# 03_pushswitch.net
KiCad netlist of a schematic drawn in Altium Designer
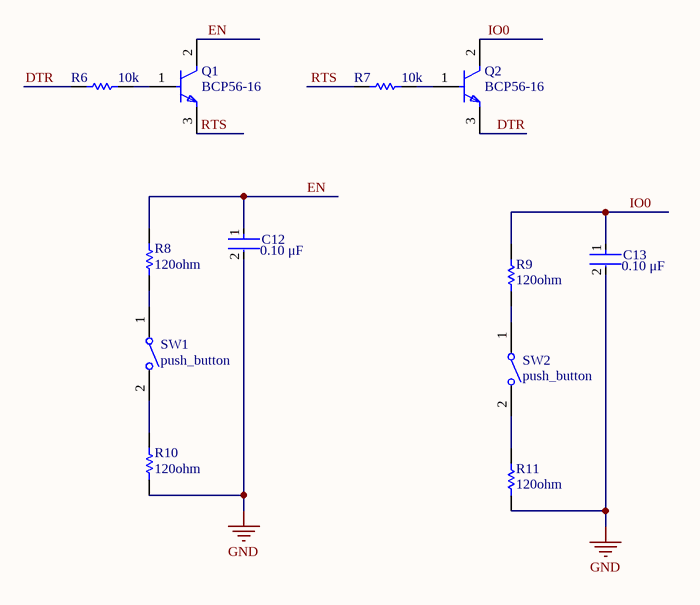
[diagram p0: 03_pushswitch.SchDoc]

(export (version "E")
  (design (tool "Eeschema 10.0.6"))
  (components
    (comp (ref "C12")
      (value "C0603_0.1UF")
      (footprint "FP-C0603C-CF-MFG")
      (description "CAP CER 0.1UF 16V X7R 0603")
      (fields
        (field (name "TOLERANCE") "0.2")
        (field (name "CAPACITANCE") "0.10 μF")
        (field (name "MANUFACTURER PART NUMBER") "C0603C104M4RAC7411")
      )
      (libsource (lib "Altium Content Vault") (part "b4654b650e69147ec39a6b967a45e02"))
    )
    (comp (ref "C13")
      (value "C0603_0.1UF")
      (footprint "FP-C0603C-CF-MFG")
      (description "CAP CER 0.1UF 16V X7R 0603")
      (fields
        (field (name "TOLERANCE") "0.2")
        (field (name "CAPACITANCE") "0.10 μF")
        (field (name "MANUFACTURER PART NUMBER") "C0603C104M4RAC7411")
      )
      (libsource (lib "Altium Content Vault") (part "b4654b650e69147ec39a6b967a45e02"))
    )
    (comp (ref "Q1")
      (value "BCP56-16")
      (footprint "FP-SOT-223-P008-MFG")
      (description "TRANS NPN 80V 1A SOT-223")
      (fields
        (field (name "OCTOPART") "https://octopart.com/bcp56-16-stmicroelectronics-13883839")
        (field (name "MANUFACTURER") "STMicroelectronics")
      )
      (libsource (lib "Altium Content Vault") (part "1c57d9dae74fe2702546667b0e849db"))
    )
    (comp (ref "Q2")
      (value "BCP56-16")
      (footprint "FP-SOT-223-P008-MFG")
      (description "TRANS NPN 80V 1A SOT-223")
      (fields
        (field (name "OCTOPART") "https://octopart.com/bcp56-16-stmicroelectronics-13883839")
        (field (name "MANUFACTURER") "STMicroelectronics")
      )
      (libsource (lib "Altium Content Vault") (part "1c57d9dae74fe2702546667b0e849db"))
    )
    (comp (ref "R6")
      (value "10k")
      (footprint "RESC1609X55X30LL15T15")
      (description "Chip Resistor, 10 KOhm, +/- 1%, 0.1 W, -55 to 155 degC, 0603 (1608 Metric), RoHS, Tape and Reel")
      (fields (field (name "TOLERANCE") "1%") (field (name "MANUFACTURER") "Panasonic"))
      (libsource (lib "Altium Content Vault") (part "RES-2"))
    )
    (comp (ref "R7")
      (value "10k")
      (footprint "RESC1609X55X30LL15T15")
      (description "Chip Resistor, 10 KOhm, +/- 1%, 0.1 W, -55 to 155 degC, 0603 (1608 Metric), RoHS, Tape and Reel")
      (fields (field (name "TOLERANCE") "1%") (field (name "MANUFACTURER") "Panasonic"))
      (libsource (lib "Altium Content Vault") (part "RES-2"))
    )
    (comp (ref "R8")
      (value "120ohm")
      (footprint "RESC1608X55X30NL20T20")
      (fields
        (field (name "PART NUMBER") "ERA-3AEB121V")
        (field (name "MANUFACTURER") "Panasonic")
        (field (name "Comment") "R0603_120R")
      )
      (libsource (lib "Altium Content Vault") (part "RES"))
    )
    (comp (ref "R9")
      (value "120ohm")
      (footprint "RESC1608X55X30NL20T20")
      (fields
        (field (name "PART NUMBER") "ERA-3AEB121V")
        (field (name "MANUFACTURER") "Panasonic")
        (field (name "Comment") "R0603_120R")
      )
      (libsource (lib "Altium Content Vault") (part "RES"))
    )
    (comp (ref "R10")
      (value "120ohm")
      (footprint "RESC1608X55X30NL20T20")
      (fields
        (field (name "PART NUMBER") "ERA-3AEB121V")
        (field (name "MANUFACTURER") "Panasonic")
        (field (name "Comment") "R0603_120R")
      )
      (libsource (lib "Altium Content Vault") (part "RES"))
    )
    (comp (ref "R11")
      (value "120ohm")
      (footprint "RESC1608X55X30NL20T20")
      (fields
        (field (name "PART NUMBER") "ERA-3AEB121V")
        (field (name "MANUFACTURER") "Panasonic")
        (field (name "Comment") "R0603_120R")
      )
      (libsource (lib "Altium Content Vault") (part "RES"))
    )
    (comp (ref "SW1")
      (value "push_button")
      (footprint "TECO-FSMSMTR_V")
      (description "FSMSM Push Button Switch, 50 mA, -35 to 85 degC, 2-Pin SMD, RoHS, Tape and Reel")
      (fields (field (name "MANUFACTURER") "TE Connectivity"))
      (libsource (lib "Altium Content Vault") (part "SW-SPST-2_C"))
    )
    (comp (ref "SW2")
      (value "push_button")
      (footprint "TECO-FSMSMTR_V")
      (description "FSMSM Push Button Switch, 50 mA, -35 to 85 degC, 2-Pin SMD, RoHS, Tape and Reel")
      (fields (field (name "MANUFACTURER") "TE Connectivity"))
      (libsource (lib "Altium Content Vault") (part "SW-SPST-2_C"))
    )
  )
  (nets
    (net (code "1") (name "/DTR") (class "Default")
      (node (ref "Q2") (pin "3") (pinfunction "E_3") (pintype "passive"))
      (node (ref "R6") (pin "1") (pinfunction "1_1") (pintype "passive"))
    )
    (net (code "2") (name "/EN") (class "Default")
      (node (ref "C12") (pin "1") (pinfunction "1_1") (pintype "passive"))
      (node (ref "Q1") (pin "2") (pinfunction "C_2") (pintype "passive"))
      (node (ref "R8") (pin "2") (pinfunction "2_2") (pintype "passive"))
    )
    (net (code "3") (name "/IO0") (class "Default")
      (node (ref "C13") (pin "1") (pinfunction "1_1") (pintype "passive"))
      (node (ref "Q2") (pin "2") (pinfunction "C_2") (pintype "passive"))
      (node (ref "R9") (pin "2") (pinfunction "2_2") (pintype "passive"))
    )
    (net (code "4") (name "/RTS") (class "Default")
      (node (ref "Q1") (pin "3") (pinfunction "E_3") (pintype "passive"))
      (node (ref "R7") (pin "1") (pinfunction "1_1") (pintype "passive"))
    )
    (net (code "5") (name "GND") (class "Default")
      (node (ref "C12") (pin "2") (pinfunction "2_2") (pintype "passive"))
      (node (ref "C13") (pin "2") (pinfunction "2_2") (pintype "passive"))
      (node (ref "R10") (pin "1") (pinfunction "1_1") (pintype "passive"))
      (node (ref "R11") (pin "1") (pinfunction "1_1") (pintype "passive"))
    )
    (net (code "6") (name "Net-(Q1-B)") (class "Default")
      (node (ref "Q1") (pin "1") (pinfunction "B_1") (pintype "passive"))
      (node (ref "R6") (pin "2") (pinfunction "2_2") (pintype "passive"))
    )
    (net (code "7") (name "Net-(Q2-B)") (class "Default")
      (node (ref "Q2") (pin "1") (pinfunction "B_1") (pintype "passive"))
      (node (ref "R7") (pin "2") (pinfunction "2_2") (pintype "passive"))
    )
    (net (code "8") (name "Net-(R8-Pad1)") (class "Default")
      (node (ref "R8") (pin "1") (pinfunction "1_1") (pintype "passive"))
      (node (ref "SW1") (pin "1") (pinfunction "1_1") (pintype "passive"))
    )
    (net (code "9") (name "Net-(R9-Pad1)") (class "Default")
      (node (ref "R9") (pin "1") (pinfunction "1_1") (pintype "passive"))
      (node (ref "SW2") (pin "1") (pinfunction "1_1") (pintype "passive"))
    )
    (net (code "10") (name "Net-(R10-Pad2)") (class "Default")
      (node (ref "R10") (pin "2") (pinfunction "2_2") (pintype "passive"))
      (node (ref "SW1") (pin "2") (pinfunction "2_2") (pintype "passive"))
    )
    (net (code "11") (name "Net-(R11-Pad2)") (class "Default")
      (node (ref "R11") (pin "2") (pinfunction "2_2") (pintype "passive"))
      (node (ref "SW2") (pin "2") (pinfunction "2_2") (pintype "passive"))
    )
  )
)
